# fie.net
KiCad netlist of a schematic drawn in EAGLE
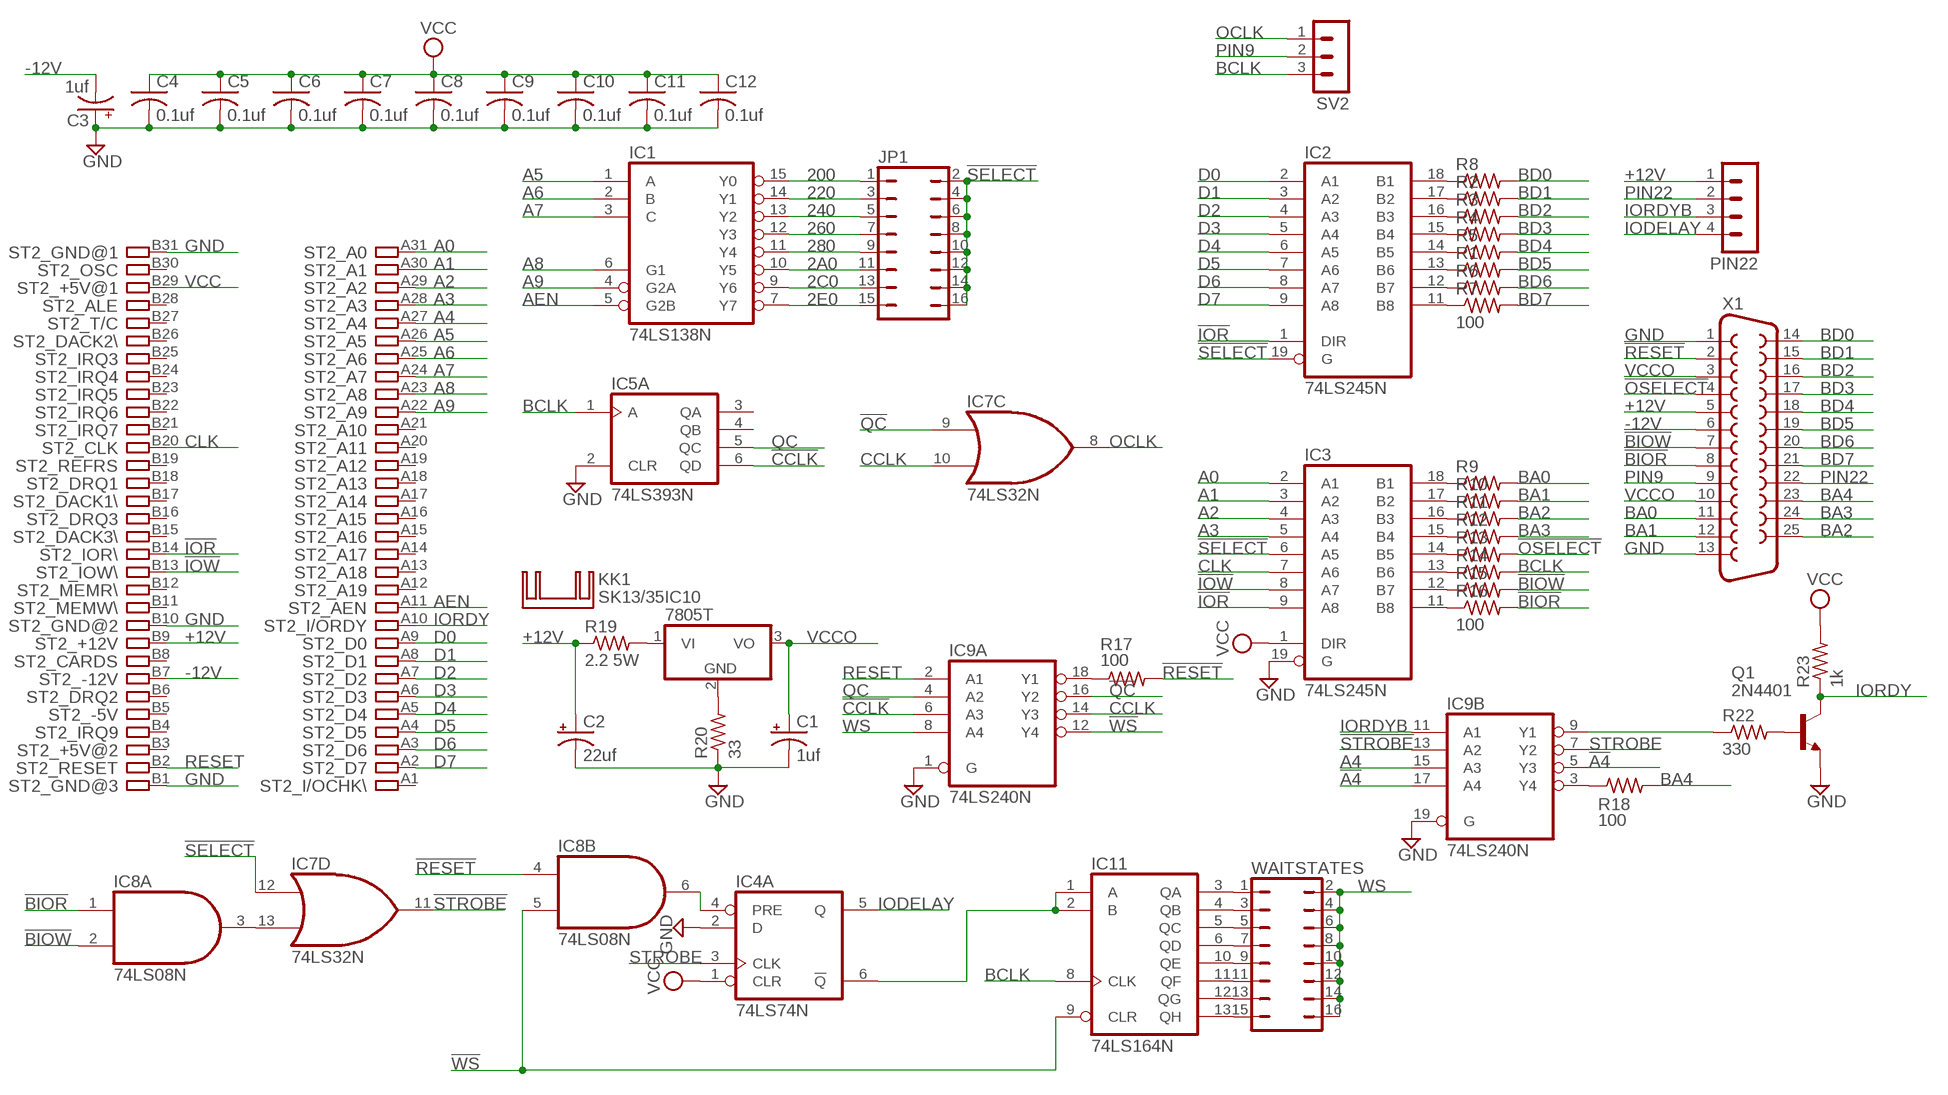
[diagram p0: schematic, sheet 1]

(export (version "E")
  (design (tool "Eeschema 10.0.6"))
  (components
    (comp (ref "C1")
      (value "1uf")
      (footprint "eagle-import:E5-10,5")
      (libsource (lib "eagle-import") (part "CPOL-USE5-10.5"))
    )
    (comp (ref "C2")
      (value "22uf")
      (footprint "eagle-import:E5-10,5")
      (libsource (lib "eagle-import") (part "CPOL-USE5-10.5"))
    )
    (comp (ref "C3")
      (value "1uf")
      (footprint "eagle-import:E5-10,5")
      (libsource (lib "eagle-import") (part "CPOL-USE5-10.5"))
    )
    (comp (ref "C4")
      (value "0.1uf")
      (footprint "eagle-import:C050-025X075")
      (libsource (lib "eagle-import") (part "C-US050-025X075"))
    )
    (comp (ref "C5")
      (value "0.1uf")
      (footprint "eagle-import:C050-025X075")
      (libsource (lib "eagle-import") (part "C-US050-025X075"))
    )
    (comp (ref "C6")
      (value "0.1uf")
      (footprint "eagle-import:C050-025X075")
      (libsource (lib "eagle-import") (part "C-US050-025X075"))
    )
    (comp (ref "C7")
      (value "0.1uf")
      (footprint "eagle-import:C050-025X075")
      (libsource (lib "eagle-import") (part "C-US050-025X075"))
    )
    (comp (ref "C8")
      (value "0.1uf")
      (footprint "eagle-import:C050-025X075")
      (libsource (lib "eagle-import") (part "C-US050-025X075"))
    )
    (comp (ref "C9")
      (value "0.1uf")
      (footprint "eagle-import:C050-025X075")
      (libsource (lib "eagle-import") (part "C-US050-025X075"))
    )
    (comp (ref "C10")
      (value "0.1uf")
      (footprint "eagle-import:C050-025X075")
      (libsource (lib "eagle-import") (part "C-US050-025X075"))
    )
    (comp (ref "C11")
      (value "0.1uf")
      (footprint "eagle-import:C050-025X075")
      (libsource (lib "eagle-import") (part "C-US050-025X075"))
    )
    (comp (ref "C12")
      (value "0.1uf")
      (footprint "eagle-import:C050-025X075")
      (libsource (lib "eagle-import") (part "C-US050-025X075"))
    )
    (comp (ref "IC1")
      (value "74LS138N")
      (footprint "eagle-import:DIL16")
      (libsource (lib "eagle-import") (part "74138NLS"))
    )
    (comp (ref "IC2")
      (value "74LS245N")
      (footprint "eagle-import:DIL20")
      (libsource (lib "eagle-import") (part "74245NLS"))
    )
    (comp (ref "IC3")
      (value "74LS245N")
      (footprint "eagle-import:DIL20")
      (libsource (lib "eagle-import") (part "74245NLS"))
    )
    (comp (ref "IC4")
      (value "74LS74N")
      (footprint "eagle-import:DIL14")
      (libsource (lib "eagle-import") (part "7474NLS"))
    )
    (comp (ref "IC5")
      (value "74LS393N")
      (footprint "eagle-import:DIL14")
      (libsource (lib "eagle-import") (part "74393NLS"))
    )
    (comp (ref "IC7")
      (value "74LS32N")
      (footprint "eagle-import:DIL14")
      (libsource (lib "eagle-import") (part "7432NLS"))
    )
    (comp (ref "IC8")
      (value "74LS08N")
      (footprint "eagle-import:DIL14")
      (libsource (lib "eagle-import") (part "7408NLS"))
    )
    (comp (ref "IC9")
      (value "74LS240N")
      (footprint "eagle-import:DIL20")
      (libsource (lib "eagle-import") (part "74240NLS"))
    )
    (comp (ref "IC10")
      (value "7805T")
      (footprint "eagle-import:TO220H")
      (libsource (lib "eagle-import") (part "78T05"))
    )
    (comp (ref "IC11")
      (value "74LS164N")
      (footprint "eagle-import:DIL14")
      (libsource (lib "eagle-import") (part "74164NLS"))
    )
    (comp (ref "JP1")
      (value "JP8Q")
      (footprint "eagle-import:JP8Q")
      (libsource (lib "eagle-import") (part "JP8Q"))
    )
    (comp (ref "KK1")
      (value "SK13/35")
      (footprint "eagle-import:SK13_35")
      (libsource (lib "eagle-import") (part "SK13/35"))
    )
    (comp (ref "PIN22")
      (value "MA04-1")
      (footprint "eagle-import:MA04-1")
      (libsource (lib "eagle-import") (part "MA04-1"))
    )
    (comp (ref "Q1")
      (value "2N4401")
      (footprint "eagle-import:TO92")
      (libsource (lib "eagle-import") (part "2N4416"))
    )
    (comp (ref "R1")
      (value "R-US_0207/10")
      (footprint "eagle-import:0207_10")
      (libsource (lib "eagle-import") (part "R-US_0207/10"))
    )
    (comp (ref "R2")
      (value "R-US_0207/10")
      (footprint "eagle-import:0207_10")
      (libsource (lib "eagle-import") (part "R-US_0207/10"))
    )
    (comp (ref "R3")
      (value "R-US_0207/10")
      (footprint "eagle-import:0207_10")
      (libsource (lib "eagle-import") (part "R-US_0207/10"))
    )
    (comp (ref "R4")
      (value "R-US_0207/10")
      (footprint "eagle-import:0207_10")
      (libsource (lib "eagle-import") (part "R-US_0207/10"))
    )
    (comp (ref "R5")
      (value "R-US_0207/10")
      (footprint "eagle-import:0207_10")
      (libsource (lib "eagle-import") (part "R-US_0207/10"))
    )
    (comp (ref "R6")
      (value "R-US_0207/10")
      (footprint "eagle-import:0207_10")
      (libsource (lib "eagle-import") (part "R-US_0207/10"))
    )
    (comp (ref "R7")
      (value "100")
      (footprint "eagle-import:0207_10")
      (libsource (lib "eagle-import") (part "R-US_0207/10"))
    )
    (comp (ref "R8")
      (value "R-US_0207/10")
      (footprint "eagle-import:0207_10")
      (libsource (lib "eagle-import") (part "R-US_0207/10"))
    )
    (comp (ref "R9")
      (value "R-US_0207/10")
      (footprint "eagle-import:0207_10")
      (libsource (lib "eagle-import") (part "R-US_0207/10"))
    )
    (comp (ref "R10")
      (value "R-US_0207/10")
      (footprint "eagle-import:0207_10")
      (libsource (lib "eagle-import") (part "R-US_0207/10"))
    )
    (comp (ref "R11")
      (value "R-US_0207/10")
      (footprint "eagle-import:0207_10")
      (libsource (lib "eagle-import") (part "R-US_0207/10"))
    )
    (comp (ref "R12")
      (value "R-US_0207/10")
      (footprint "eagle-import:0207_10")
      (libsource (lib "eagle-import") (part "R-US_0207/10"))
    )
    (comp (ref "R13")
      (value "R-US_0207/10")
      (footprint "eagle-import:0207_10")
      (libsource (lib "eagle-import") (part "R-US_0207/10"))
    )
    (comp (ref "R14")
      (value "R-US_0207/10")
      (footprint "eagle-import:0207_10")
      (libsource (lib "eagle-import") (part "R-US_0207/10"))
    )
    (comp (ref "R15")
      (value "R-US_0207/10")
      (footprint "eagle-import:0207_10")
      (libsource (lib "eagle-import") (part "R-US_0207/10"))
    )
    (comp (ref "R16")
      (value "100")
      (footprint "eagle-import:0207_10")
      (libsource (lib "eagle-import") (part "R-US_0207/10"))
    )
    (comp (ref "R17")
      (value "100")
      (footprint "eagle-import:0207_10")
      (libsource (lib "eagle-import") (part "R-US_0207/10"))
    )
    (comp (ref "R18")
      (value "100")
      (footprint "eagle-import:0207_10")
      (libsource (lib "eagle-import") (part "R-US_0207/10"))
    )
    (comp (ref "R19")
      (value "2.2 5W")
      (footprint "eagle-import:0922_22")
      (libsource (lib "eagle-import") (part "R-US_0922/22"))
    )
    (comp (ref "R20")
      (value "33")
      (footprint "eagle-import:0207_10")
      (libsource (lib "eagle-import") (part "R-US_0207/10"))
    )
    (comp (ref "R22")
      (value "330")
      (footprint "eagle-import:0207_10")
      (libsource (lib "eagle-import") (part "R-US_0207/10"))
    )
    (comp (ref "R23")
      (value "1k")
      (footprint "eagle-import:0207_10")
      (libsource (lib "eagle-import") (part "R-US_0207/10"))
    )
    (comp (ref "ST2")
      (value "IBM8BIT")
      (footprint "eagle-import:IBM8BIT")
      (libsource (lib "eagle-import") (part "IBM8BIT"))
    )
    (comp (ref "SV2")
      (value "MA03-1")
      (footprint "eagle-import:MA03-1")
      (libsource (lib "eagle-import") (part "MA03-1"))
    )
    (comp (ref "WAITSTATES")
      (value "JP8Q")
      (footprint "eagle-import:JP8Q")
      (libsource (lib "eagle-import") (part "JP8Q"))
    )
    (comp (ref "X1")
      (value "F25H")
      (footprint "eagle-import:F25H")
      (libsource (lib "eagle-import") (part "F25H"))
    )
  )
  (nets
    (net (code "1") (name "/+12V") (class "Default")
      (node (ref "C2") (pin "+") (pinfunction "+_+") (pintype "passive"))
      (node (ref "PIN22") (pin "1") (pinfunction "1_1") (pintype "passive"))
      (node (ref "R19") (pin "1") (pinfunction "1_1") (pintype "passive"))
      (node (ref "ST2") (pin "B9") (pinfunction "P_B9") (pintype "bidirectional"))
      (node (ref "X1") (pin "5") (pinfunction "5_5") (pintype "passive"))
    )
    (net (code "2") (name "/-12V") (class "Default")
      (node (ref "C3") (pin "-") (pinfunction "-_-") (pintype "passive"))
      (node (ref "ST2") (pin "B7") (pinfunction "P_B7") (pintype "bidirectional"))
      (node (ref "X1") (pin "6") (pinfunction "6_6") (pintype "passive"))
    )
    (net (code "3") (name "/2A0") (class "Default")
      (node (ref "IC1") (pin "10") (pinfunction "Y5_10") (pintype "output"))
      (node (ref "JP1") (pin "11") (pinfunction "11_11") (pintype "passive"))
    )
    (net (code "4") (name "/2C0") (class "Default")
      (node (ref "IC1") (pin "9") (pinfunction "Y6_9") (pintype "output"))
      (node (ref "JP1") (pin "13") (pinfunction "13_13") (pintype "passive"))
    )
    (net (code "5") (name "/2E0") (class "Default")
      (node (ref "IC1") (pin "7") (pinfunction "Y7_7") (pintype "output"))
      (node (ref "JP1") (pin "15") (pinfunction "15_15") (pintype "passive"))
    )
    (net (code "6") (name "/200") (class "Default")
      (node (ref "IC1") (pin "15") (pinfunction "Y0_15") (pintype "output"))
      (node (ref "JP1") (pin "1") (pinfunction "1_1") (pintype "passive"))
    )
    (net (code "7") (name "/220") (class "Default")
      (node (ref "IC1") (pin "14") (pinfunction "Y1_14") (pintype "output"))
      (node (ref "JP1") (pin "3") (pinfunction "3_3") (pintype "passive"))
    )
    (net (code "8") (name "/240") (class "Default")
      (node (ref "IC1") (pin "13") (pinfunction "Y2_13") (pintype "output"))
      (node (ref "JP1") (pin "5") (pinfunction "5_5") (pintype "passive"))
    )
    (net (code "9") (name "/260") (class "Default")
      (node (ref "IC1") (pin "12") (pinfunction "Y3_12") (pintype "output"))
      (node (ref "JP1") (pin "7") (pinfunction "7_7") (pintype "passive"))
    )
    (net (code "10") (name "/280") (class "Default")
      (node (ref "IC1") (pin "11") (pinfunction "Y4_11") (pintype "output"))
      (node (ref "JP1") (pin "9") (pinfunction "9_9") (pintype "passive"))
    )
    (net (code "11") (name "/A0") (class "Default")
      (node (ref "IC3") (pin "2") (pinfunction "A1_2") (pintype "bidirectional"))
      (node (ref "ST2") (pin "A31") (pinfunction "P_A31") (pintype "bidirectional"))
    )
    (net (code "12") (name "/A1") (class "Default")
      (node (ref "IC3") (pin "3") (pinfunction "A2_3") (pintype "bidirectional"))
      (node (ref "ST2") (pin "A30") (pinfunction "P_A30") (pintype "bidirectional"))
    )
    (net (code "13") (name "/A2") (class "Default")
      (node (ref "IC3") (pin "4") (pinfunction "A3_4") (pintype "bidirectional"))
      (node (ref "ST2") (pin "A29") (pinfunction "P_A29") (pintype "bidirectional"))
    )
    (net (code "14") (name "/A3") (class "Default")
      (node (ref "IC3") (pin "5") (pinfunction "A4_5") (pintype "bidirectional"))
      (node (ref "ST2") (pin "A28") (pinfunction "P_A28") (pintype "bidirectional"))
    )
    (net (code "15") (name "/A4") (class "Default")
      (node (ref "IC9") (pin "15") (pinfunction "A3_15") (pintype "input"))
      (node (ref "ST2") (pin "A27") (pinfunction "P_A27") (pintype "bidirectional"))
    )
    (net (code "16") (name "/A5") (class "Default")
      (node (ref "IC1") (pin "1") (pinfunction "A_1") (pintype "input"))
      (node (ref "ST2") (pin "A26") (pinfunction "P_A26") (pintype "bidirectional"))
    )
    (net (code "17") (name "/A6") (class "Default")
      (node (ref "IC1") (pin "2") (pinfunction "B_2") (pintype "input"))
      (node (ref "ST2") (pin "A25") (pinfunction "P_A25") (pintype "bidirectional"))
    )
    (net (code "18") (name "/A7") (class "Default")
      (node (ref "IC1") (pin "3") (pinfunction "C_3") (pintype "input"))
      (node (ref "ST2") (pin "A24") (pinfunction "P_A24") (pintype "bidirectional"))
    )
    (net (code "19") (name "/A8") (class "Default")
      (node (ref "IC1") (pin "6") (pinfunction "G1_6") (pintype "input"))
      (node (ref "ST2") (pin "A23") (pinfunction "P_A23") (pintype "bidirectional"))
    )
    (net (code "20") (name "/A9") (class "Default")
      (node (ref "IC1") (pin "4") (pinfunction "G2A_4") (pintype "input"))
      (node (ref "ST2") (pin "A22") (pinfunction "P_A22") (pintype "bidirectional"))
    )
    (net (code "21") (name "/AEN") (class "Default")
      (node (ref "IC1") (pin "5") (pinfunction "G2B_5") (pintype "input"))
      (node (ref "ST2") (pin "A11") (pinfunction "P_A11") (pintype "bidirectional"))
    )
    (net (code "22") (name "/BA0") (class "Default")
      (node (ref "R9") (pin "2") (pinfunction "2_2") (pintype "passive"))
      (node (ref "X1") (pin "11") (pinfunction "11_11") (pintype "passive"))
    )
    (net (code "23") (name "/BA1") (class "Default")
      (node (ref "R10") (pin "2") (pinfunction "2_2") (pintype "passive"))
      (node (ref "X1") (pin "12") (pinfunction "12_12") (pintype "passive"))
    )
    (net (code "24") (name "/BA2") (class "Default")
      (node (ref "R11") (pin "2") (pinfunction "2_2") (pintype "passive"))
      (node (ref "X1") (pin "25") (pinfunction "25_25") (pintype "passive"))
    )
    (net (code "25") (name "/BA3") (class "Default")
      (node (ref "R12") (pin "2") (pinfunction "2_2") (pintype "passive"))
      (node (ref "X1") (pin "24") (pinfunction "24_24") (pintype "passive"))
    )
    (net (code "26") (name "/BA4") (class "Default")
      (node (ref "R18") (pin "2") (pinfunction "2_2") (pintype "passive"))
      (node (ref "X1") (pin "23") (pinfunction "23_23") (pintype "passive"))
    )
    (net (code "27") (name "/BCLK") (class "Default")
      (node (ref "IC11") (pin "8") (pinfunction "CLK_8") (pintype "input"))
      (node (ref "IC5") (pin "1") (pinfunction "A_1") (pintype "input"))
      (node (ref "R14") (pin "2") (pinfunction "2_2") (pintype "passive"))
      (node (ref "SV2") (pin "3") (pinfunction "3_3") (pintype "passive"))
    )
    (net (code "28") (name "/BD0") (class "Default")
      (node (ref "R8") (pin "2") (pinfunction "2_2") (pintype "passive"))
      (node (ref "X1") (pin "14") (pinfunction "14_14") (pintype "passive"))
    )
    (net (code "29") (name "/BD1") (class "Default")
      (node (ref "R2") (pin "2") (pinfunction "2_2") (pintype "passive"))
      (node (ref "X1") (pin "15") (pinfunction "15_15") (pintype "passive"))
    )
    (net (code "30") (name "/BD2") (class "Default")
      (node (ref "R3") (pin "2") (pinfunction "2_2") (pintype "passive"))
      (node (ref "X1") (pin "16") (pinfunction "16_16") (pintype "passive"))
    )
    (net (code "31") (name "/BD3") (class "Default")
      (node (ref "R4") (pin "2") (pinfunction "2_2") (pintype "passive"))
      (node (ref "X1") (pin "17") (pinfunction "17_17") (pintype "passive"))
    )
    (net (code "32") (name "/BD4") (class "Default")
      (node (ref "R5") (pin "2") (pinfunction "2_2") (pintype "passive"))
      (node (ref "X1") (pin "18") (pinfunction "18_18") (pintype "passive"))
    )
    (net (code "33") (name "/BD5") (class "Default")
      (node (ref "R1") (pin "2") (pinfunction "2_2") (pintype "passive"))
      (node (ref "X1") (pin "19") (pinfunction "19_19") (pintype "passive"))
    )
    (net (code "34") (name "/BD6") (class "Default")
      (node (ref "R6") (pin "2") (pinfunction "2_2") (pintype "passive"))
      (node (ref "X1") (pin "20") (pinfunction "20_20") (pintype "passive"))
    )
    (net (code "35") (name "/BD7") (class "Default")
      (node (ref "R7") (pin "2") (pinfunction "2_2") (pintype "passive"))
      (node (ref "X1") (pin "21") (pinfunction "21_21") (pintype "passive"))
    )
    (net (code "36") (name "/CCLK") (class "Default")
      (node (ref "IC7") (pin "10") (pinfunction "I1_10") (pintype "input"))
      (node (ref "IC9") (pin "14") (pinfunction "Y3_14") (pintype "tri_state"))
    )
    (net (code "37") (name "/CLK") (class "Default")
      (node (ref "IC3") (pin "7") (pinfunction "A6_7") (pintype "bidirectional"))
      (node (ref "ST2") (pin "B20") (pinfunction "P_B20") (pintype "bidirectional"))
    )
    (net (code "38") (name "/D0") (class "Default")
      (node (ref "IC2") (pin "2") (pinfunction "A1_2") (pintype "bidirectional"))
      (node (ref "ST2") (pin "A9") (pinfunction "P_A9") (pintype "bidirectional"))
    )
    (net (code "39") (name "/D1") (class "Default")
      (node (ref "IC2") (pin "3") (pinfunction "A2_3") (pintype "bidirectional"))
      (node (ref "ST2") (pin "A8") (pinfunction "P_A8") (pintype "bidirectional"))
    )
    (net (code "40") (name "/D2") (class "Default")
      (node (ref "IC2") (pin "4") (pinfunction "A3_4") (pintype "bidirectional"))
      (node (ref "ST2") (pin "A7") (pinfunction "P_A7") (pintype "bidirectional"))
    )
    (net (code "41") (name "/D3") (class "Default")
      (node (ref "IC2") (pin "5") (pinfunction "A4_5") (pintype "bidirectional"))
      (node (ref "ST2") (pin "A6") (pinfunction "P_A6") (pintype "bidirectional"))
    )
    (net (code "42") (name "/D4") (class "Default")
      (node (ref "IC2") (pin "6") (pinfunction "A5_6") (pintype "bidirectional"))
      (node (ref "ST2") (pin "A5") (pinfunction "P_A5") (pintype "bidirectional"))
    )
    (net (code "43") (name "/D5") (class "Default")
      (node (ref "IC2") (pin "7") (pinfunction "A6_7") (pintype "bidirectional"))
      (node (ref "ST2") (pin "A4") (pinfunction "P_A4") (pintype "bidirectional"))
    )
    (net (code "44") (name "/D6") (class "Default")
      (node (ref "IC2") (pin "8") (pinfunction "A7_8") (pintype "bidirectional"))
      (node (ref "ST2") (pin "A3") (pinfunction "P_A3") (pintype "bidirectional"))
    )
    (net (code "45") (name "/D7") (class "Default")
      (node (ref "IC2") (pin "9") (pinfunction "A8_9") (pintype "bidirectional"))
      (node (ref "ST2") (pin "A2") (pinfunction "P_A2") (pintype "bidirectional"))
    )
    (net (code "46") (name "/IODELAY") (class "Default")
      (node (ref "IC4") (pin "5") (pinfunction "Q_5") (pintype "output"))
      (node (ref "PIN22") (pin "4") (pinfunction "4_4") (pintype "passive"))
    )
    (net (code "47") (name "/IORDY") (class "Default")
      (node (ref "Q1") (pin "1") (pinfunction "C_1") (pintype "passive"))
      (node (ref "R23") (pin "1") (pinfunction "1_1") (pintype "passive"))
      (node (ref "ST2") (pin "A10") (pinfunction "P_A10") (pintype "bidirectional"))
    )
    (net (code "48") (name "/IORDYB") (class "Default")
      (node (ref "IC9") (pin "11") (pinfunction "A1_11") (pintype "input"))
      (node (ref "PIN22") (pin "3") (pinfunction "3_3") (pintype "passive"))
    )
    (net (code "49") (name "/OCLK") (class "Default")
      (node (ref "IC7") (pin "8") (pinfunction "O_8") (pintype "output"))
      (node (ref "SV2") (pin "1") (pinfunction "1_1") (pintype "passive"))
    )
    (net (code "50") (name "/PIN9") (class "Default")
      (node (ref "SV2") (pin "2") (pinfunction "2_2") (pintype "passive"))
      (node (ref "X1") (pin "9") (pinfunction "9_9") (pintype "passive"))
    )
    (net (code "51") (name "/PIN22") (class "Default")
      (node (ref "PIN22") (pin "2") (pinfunction "2_2") (pintype "passive"))
      (node (ref "X1") (pin "22") (pinfunction "22_22") (pintype "passive"))
    )
    (net (code "52") (name "/QC") (class "Default")
      (node (ref "IC5") (pin "5") (pinfunction "QC_5") (pintype "output"))
      (node (ref "IC9") (pin "4") (pinfunction "A2_4") (pintype "input"))
    )
    (net (code "53") (name "/RESET") (class "Default")
      (node (ref "IC9") (pin "2") (pinfunction "A1_2") (pintype "input"))
      (node (ref "ST2") (pin "B2") (pinfunction "P_B2") (pintype "bidirectional"))
    )
    (net (code "54") (name "/STROBE") (class "Default")
      (node (ref "IC4") (pin "3") (pinfunction "CLK_3") (pintype "input"))
      (node (ref "IC9") (pin "7") (pinfunction "Y2_7") (pintype "tri_state"))
    )
    (net (code "55") (name "/VCCO") (class "Default")
      (node (ref "C1") (pin "+") (pinfunction "+_+") (pintype "passive"))
      (node (ref "IC10") (pin "3") (pinfunction "VO_3") (pintype "passive"))
      (node (ref "X1") (pin "10") (pinfunction "10_10") (pintype "passive"))
      (node (ref "X1") (pin "3") (pinfunction "3_3") (pintype "passive"))
    )
    (net (code "56") (name "/WS") (class "Default")
      (node (ref "IC9") (pin "8") (pinfunction "A4_8") (pintype "input"))
      (node (ref "WAITSTATES") (pin "10") (pinfunction "10_10") (pintype "passive"))
      (node (ref "WAITSTATES") (pin "12") (pinfunction "12_12") (pintype "passive"))
      (node (ref "WAITSTATES") (pin "14") (pinfunction "14_14") (pintype "passive"))
      (node (ref "WAITSTATES") (pin "16") (pinfunction "16_16") (pintype "passive"))
      (node (ref "WAITSTATES") (pin "2") (pinfunction "2_2") (pintype "passive"))
      (node (ref "WAITSTATES") (pin "4") (pinfunction "4_4") (pintype "passive"))
      (node (ref "WAITSTATES") (pin "6") (pinfunction "6_6") (pintype "passive"))
      (node (ref "WAITSTATES") (pin "8") (pinfunction "8_8") (pintype "passive"))
    )
    (net (code "57") (name "/~{A4}") (class "Default")
      (node (ref "IC9") (pin "17") (pinfunction "A4_17") (pintype "input"))
      (node (ref "IC9") (pin "5") (pinfunction "Y3_5") (pintype "tri_state"))
    )
    (net (code "58") (name "/~{BIOR}") (class "Default")
      (node (ref "IC8") (pin "1") (pinfunction "I0_1") (pintype "input"))
      (node (ref "R16") (pin "2") (pinfunction "2_2") (pintype "passive"))
      (node (ref "X1") (pin "8") (pinfunction "8_8") (pintype "passive"))
    )
    (net (code "59") (name "/~{BIOW}") (class "Default")
      (node (ref "IC8") (pin "2") (pinfunction "I1_2") (pintype "input"))
      (node (ref "R15") (pin "2") (pinfunction "2_2") (pintype "passive"))
      (node (ref "X1") (pin "7") (pinfunction "7_7") (pintype "passive"))
    )
    (net (code "60") (name "/~{CCLK}") (class "Default")
      (node (ref "IC5") (pin "6") (pinfunction "QD_6") (pintype "output"))
      (node (ref "IC9") (pin "6") (pinfunction "A3_6") (pintype "input"))
    )
    (net (code "61") (name "/~{IOR}") (class "Default")
      (node (ref "IC2") (pin "1") (pinfunction "DIR_1") (pintype "input"))
      (node (ref "IC3") (pin "9") (pinfunction "A8_9") (pintype "bidirectional"))
      (node (ref "ST2") (pin "B14") (pinfunction "P_B14") (pintype "bidirectional"))
    )
    (net (code "62") (name "/~{IOW}") (class "Default")
      (node (ref "IC3") (pin "8") (pinfunction "A7_8") (pintype "bidirectional"))
      (node (ref "ST2") (pin "B13") (pinfunction "P_B13") (pintype "bidirectional"))
    )
    (net (code "63") (name "/~{OSELECT}") (class "Default")
      (node (ref "R13") (pin "2") (pinfunction "2_2") (pintype "passive"))
      (node (ref "X1") (pin "4") (pinfunction "4_4") (pintype "passive"))
    )
    (net (code "64") (name "/~{QC}") (class "Default")
      (node (ref "IC7") (pin "9") (pinfunction "I0_9") (pintype "input"))
      (node (ref "IC9") (pin "16") (pinfunction "Y2_16") (pintype "tri_state"))
    )
    (net (code "65") (name "/~{RESET}") (class "Default")
      (node (ref "IC8") (pin "4") (pinfunction "I0_4") (pintype "input"))
      (node (ref "R17") (pin "2") (pinfunction "2_2") (pintype "passive"))
      (node (ref "X1") (pin "2") (pinfunction "2_2") (pintype "passive"))
    )
    (net (code "66") (name "/~{SELECT}") (class "Default")
      (node (ref "IC2") (pin "19") (pinfunction "G_19") (pintype "input"))
      (node (ref "IC3") (pin "6") (pinfunction "A5_6") (pintype "bidirectional"))
      (node (ref "IC7") (pin "12") (pinfunction "I0_12") (pintype "input"))
      (node (ref "JP1") (pin "10") (pinfunction "10_10") (pintype "passive"))
      (node (ref "JP1") (pin "12") (pinfunction "12_12") (pintype "passive"))
      (node (ref "JP1") (pin "14") (pinfunction "14_14") (pintype "passive"))
      (node (ref "JP1") (pin "16") (pinfunction "16_16") (pintype "passive"))
      (node (ref "JP1") (pin "2") (pinfunction "2_2") (pintype "passive"))
      (node (ref "JP1") (pin "4") (pinfunction "4_4") (pintype "passive"))
      (node (ref "JP1") (pin "6") (pinfunction "6_6") (pintype "passive"))
      (node (ref "JP1") (pin "8") (pinfunction "8_8") (pintype "passive"))
    )
    (net (code "67") (name "/~{STROBE}") (class "Default")
      (node (ref "IC7") (pin "11") (pinfunction "O_11") (pintype "output"))
      (node (ref "IC9") (pin "13") (pinfunction "A2_13") (pintype "input"))
    )
    (net (code "68") (name "/~{WS}") (class "Default")
      (node (ref "IC11") (pin "9") (pinfunction "CLR_9") (pintype "input"))
      (node (ref "IC8") (pin "5") (pinfunction "I1_5") (pintype "input"))
      (node (ref "IC9") (pin "12") (pinfunction "Y4_12") (pintype "tri_state"))
    )
    (net (code "69") (name "GND") (class "Default")
      (node (ref "C1") (pin "-") (pinfunction "-_-") (pintype "passive"))
      (node (ref "C10") (pin "2") (pinfunction "2_2") (pintype "passive"))
      (node (ref "C11") (pin "2") (pinfunction "2_2") (pintype "passive"))
      (node (ref "C12") (pin "2") (pinfunction "2_2") (pintype "passive"))
      (node (ref "C2") (pin "-") (pinfunction "-_-") (pintype "passive"))
      (node (ref "C3") (pin "+") (pinfunction "+_+") (pintype "passive"))
      (node (ref "C4") (pin "2") (pinfunction "2_2") (pintype "passive"))
      (node (ref "C5") (pin "2") (pinfunction "2_2") (pintype "passive"))
      (node (ref "C6") (pin "2") (pinfunction "2_2") (pintype "passive"))
      (node (ref "C7") (pin "2") (pinfunction "2_2") (pintype "passive"))
      (node (ref "C8") (pin "2") (pinfunction "2_2") (pintype "passive"))
      (node (ref "C9") (pin "2") (pinfunction "2_2") (pintype "passive"))
      (node (ref "IC3") (pin "19") (pinfunction "G_19") (pintype "input"))
      (node (ref "IC4") (pin "2") (pinfunction "D_2") (pintype "input"))
      (node (ref "IC5") (pin "2") (pinfunction "CLR_2") (pintype "input"))
      (node (ref "IC9") (pin "1") (pinfunction "G_1") (pintype "input"))
      (node (ref "IC9") (pin "19") (pinfunction "G_19") (pintype "input"))
      (node (ref "Q1") (pin "3") (pinfunction "E_3") (pintype "passive"))
      (node (ref "R20") (pin "1") (pinfunction "1_1") (pintype "passive"))
      (node (ref "ST2") (pin "B1") (pinfunction "P_B1") (pintype "bidirectional"))
      (node (ref "ST2") (pin "B10") (pinfunction "P_B10") (pintype "bidirectional"))
      (node (ref "ST2") (pin "B31") (pinfunction "P_B31") (pintype "bidirectional"))
      (node (ref "X1") (pin "1") (pinfunction "1_1") (pintype "passive"))
      (node (ref "X1") (pin "13") (pinfunction "13_13") (pintype "passive"))
    )
    (net (code "70") (name "Net-(IC2A-B1)") (class "Default")
      (node (ref "IC2") (pin "18") (pinfunction "B1_18") (pintype "bidirectional"))
      (node (ref "R8") (pin "1") (pinfunction "1_1") (pintype "passive"))
    )
    (net (code "71") (name "Net-(IC2A-B2)") (class "Default")
      (node (ref "IC2") (pin "17") (pinfunction "B2_17") (pintype "bidirectional"))
      (node (ref "R2") (pin "1") (pinfunction "1_1") (pintype "passive"))
    )
    (net (code "72") (name "Net-(IC2A-B3)") (class "Default")
      (node (ref "IC2") (pin "16") (pinfunction "B3_16") (pintype "bidirectional"))
      (node (ref "R3") (pin "1") (pinfunction "1_1") (pintype "passive"))
    )
    (net (code "73") (name "Net-(IC2A-B4)") (class "Default")
      (node (ref "IC2") (pin "15") (pinfunction "B4_15") (pintype "bidirectional"))
      (node (ref "R4") (pin "1") (pinfunction "1_1") (pintype "passive"))
    )
    (net (code "74") (name "Net-(IC2A-B5)") (class "Default")
      (node (ref "IC2") (pin "14") (pinfunction "B5_14") (pintype "bidirectional"))
      (node (ref "R5") (pin "1") (pinfunction "1_1") (pintype "passive"))
    )
    (net (code "75") (name "Net-(IC2A-B6)") (class "Default")
      (node (ref "IC2") (pin "13") (pinfunction "B6_13") (pintype "bidirectional"))
      (node (ref "R1") (pin "1") (pinfunction "1_1") (pintype "passive"))
    )
    (net (code "76") (name "Net-(IC2A-B7)") (class "Default")
      (node (ref "IC2") (pin "12") (pinfunction "B7_12") (pintype "bidirectional"))
      (node (ref "R6") (pin "1") (pinfunction "1_1") (pintype "passive"))
    )
    (net (code "77") (name "Net-(IC2A-B8)") (class "Default")
      (node (ref "IC2") (pin "11") (pinfunction "B8_11") (pintype "bidirectional"))
      (node (ref "R7") (pin "1") (pinfunction "1_1") (pintype "passive"))
    )
    (net (code "78") (name "Net-(IC3A-B1)") (class "Default")
      (node (ref "IC3") (pin "18") (pinfunction "B1_18") (pintype "bidirectional"))
      (node (ref "R9") (pin "1") (pinfunction "1_1") (pintype "passive"))
    )
    (net (code "79") (name "Net-(IC3A-B2)") (class "Default")
      (node (ref "IC3") (pin "17") (pinfunction "B2_17") (pintype "bidirectional"))
      (node (ref "R10") (pin "1") (pinfunction "1_1") (pintype "passive"))
    )
    (net (code "80") (name "Net-(IC3A-B3)") (class "Default")
      (node (ref "IC3") (pin "16") (pinfunction "B3_16") (pintype "bidirectional"))
      (node (ref "R11") (pin "1") (pinfunction "1_1") (pintype "passive"))
    )
    (net (code "81") (name "Net-(IC3A-B4)") (class "Default")
      (node (ref "IC3") (pin "15") (pinfunction "B4_15") (pintype "bidirectional"))
      (node (ref "R12") (pin "1") (pinfunction "1_1") (pintype "passive"))
    )
    (net (code "82") (name "Net-(IC3A-B5)") (class "Default")
      (node (ref "IC3") (pin "14") (pinfunction "B5_14") (pintype "bidirectional"))
      (node (ref "R13") (pin "1") (pinfunction "1_1") (pintype "passive"))
    )
    (net (code "83") (name "Net-(IC3A-B6)") (class "Default")
      (node (ref "IC3") (pin "13") (pinfunction "B6_13") (pintype "bidirectional"))
      (node (ref "R14") (pin "1") (pinfunction "1_1") (pintype "passive"))
    )
    (net (code "84") (name "Net-(IC3A-B7)") (class "Default")
      (node (ref "IC3") (pin "12") (pinfunction "B7_12") (pintype "bidirectional"))
      (node (ref "R15") (pin "1") (pinfunction "1_1") (pintype "passive"))
    )
    (net (code "85") (name "Net-(IC3A-B8)") (class "Default")
      (node (ref "IC3") (pin "11") (pinfunction "B8_11") (pintype "bidirectional"))
      (node (ref "R16") (pin "1") (pinfunction "1_1") (pintype "passive"))
    )
    (net (code "86") (name "Net-(IC4A-PRE)") (class "Default")
      (node (ref "IC4") (pin "4") (pinfunction "PRE_4") (pintype "input"))
      (node (ref "IC8") (pin "6") (pinfunction "O_6") (pintype "output"))
    )
    (net (code "87") (name "Net-(IC7D-I1)") (class "Default")
      (node (ref "IC7") (pin "13") (pinfunction "I1_13") (pintype "input"))
      (node (ref "IC8") (pin "3") (pinfunction "O_3") (pintype "output"))
    )
    (net (code "88") (name "Net-(IC9A-Y1)") (class "Default")
      (node (ref "IC9") (pin "18") (pinfunction "Y1_18") (pintype "tri_state"))
      (node (ref "R17") (pin "1") (pinfunction "1_1") (pintype "passive"))
    )
    (net (code "89") (name "Net-(IC9B-Y1)") (class "Default")
      (node (ref "IC9") (pin "9") (pinfunction "Y1_9") (pintype "tri_state"))
      (node (ref "R22") (pin "1") (pinfunction "1_1") (pintype "passive"))
    )
    (net (code "90") (name "Net-(IC9B-Y4)") (class "Default")
      (node (ref "IC9") (pin "3") (pinfunction "Y4_3") (pintype "tri_state"))
      (node (ref "R18") (pin "1") (pinfunction "1_1") (pintype "passive"))
    )
    (net (code "91") (name "Net-(IC10-GND)") (class "Default")
      (node (ref "IC10") (pin "2") (pinfunction "GND_2") (pintype "passive"))
      (node (ref "R20") (pin "2") (pinfunction "2_2") (pintype "passive"))
    )
    (net (code "92") (name "Net-(IC10-VI)") (class "Default")
      (node (ref "IC10") (pin "1") (pinfunction "VI_1") (pintype "input"))
      (node (ref "R19") (pin "2") (pinfunction "2_2") (pintype "passive"))
    )
    (net (code "93") (name "Net-(IC11A-A)") (class "Default")
      (node (ref "IC11") (pin "1") (pinfunction "A_1") (pintype "input"))
      (node (ref "IC11") (pin "2") (pinfunction "B_2") (pintype "input"))
      (node (ref "IC4") (pin "6") (pinfunction "~{Q}_6") (pintype "output"))
    )
    (net (code "94") (name "Net-(IC11A-QA)") (class "Default")
      (node (ref "IC11") (pin "3") (pinfunction "QA_3") (pintype "output"))
      (node (ref "WAITSTATES") (pin "1") (pinfunction "1_1") (pintype "passive"))
    )
    (net (code "95") (name "Net-(IC11A-QB)") (class "Default")
      (node (ref "IC11") (pin "4") (pinfunction "QB_4") (pintype "output"))
      (node (ref "WAITSTATES") (pin "3") (pinfunction "3_3") (pintype "passive"))
    )
    (net (code "96") (name "Net-(IC11A-QC)") (class "Default")
      (node (ref "IC11") (pin "5") (pinfunction "QC_5") (pintype "output"))
      (node (ref "WAITSTATES") (pin "5") (pinfunction "5_5") (pintype "passive"))
    )
    (net (code "97") (name "Net-(IC11A-QD)") (class "Default")
      (node (ref "IC11") (pin "6") (pinfunction "QD_6") (pintype "output"))
      (node (ref "WAITSTATES") (pin "7") (pinfunction "7_7") (pintype "passive"))
    )
    (net (code "98") (name "Net-(IC11A-QE)") (class "Default")
      (node (ref "IC11") (pin "10") (pinfunction "QE_10") (pintype "output"))
      (node (ref "WAITSTATES") (pin "9") (pinfunction "9_9") (pintype "passive"))
    )
    (net (code "99") (name "Net-(IC11A-QF)") (class "Default")
      (node (ref "IC11") (pin "11") (pinfunction "QF_11") (pintype "output"))
      (node (ref "WAITSTATES") (pin "11") (pinfunction "11_11") (pintype "passive"))
    )
    (net (code "100") (name "Net-(IC11A-QG)") (class "Default")
      (node (ref "IC11") (pin "12") (pinfunction "QG_12") (pintype "output"))
      (node (ref "WAITSTATES") (pin "13") (pinfunction "13_13") (pintype "passive"))
    )
    (net (code "101") (name "Net-(IC11A-QH)") (class "Default")
      (node (ref "IC11") (pin "13") (pinfunction "QH_13") (pintype "output"))
      (node (ref "WAITSTATES") (pin "15") (pinfunction "15_15") (pintype "passive"))
    )
    (net (code "102") (name "Net-(Q1-B)") (class "Default")
      (node (ref "Q1") (pin "2") (pinfunction "B_2") (pintype "passive"))
      (node (ref "R22") (pin "2") (pinfunction "2_2") (pintype "passive"))
    )
    (net (code "103") (name "VCC") (class "Default")
      (node (ref "C10") (pin "1") (pinfunction "1_1") (pintype "passive"))
      (node (ref "C11") (pin "1") (pinfunction "1_1") (pintype "passive"))
      (node (ref "C12") (pin "1") (pinfunction "1_1") (pintype "passive"))
      (node (ref "C4") (pin "1") (pinfunction "1_1") (pintype "passive"))
      (node (ref "C5") (pin "1") (pinfunction "1_1") (pintype "passive"))
      (node (ref "C6") (pin "1") (pinfunction "1_1") (pintype "passive"))
      (node (ref "C7") (pin "1") (pinfunction "1_1") (pintype "passive"))
      (node (ref "C8") (pin "1") (pinfunction "1_1") (pintype "passive"))
      (node (ref "C9") (pin "1") (pinfunction "1_1") (pintype "passive"))
      (node (ref "IC3") (pin "1") (pinfunction "DIR_1") (pintype "input"))
      (node (ref "IC4") (pin "1") (pinfunction "CLR_1") (pintype "input"))
      (node (ref "R23") (pin "2") (pinfunction "2_2") (pintype "passive"))
      (node (ref "ST2") (pin "B29") (pinfunction "P_B29") (pintype "bidirectional"))
    )
    (net (code "104") (name "unconnected-(IC5A-QA-Pad3)") (class "Default")
      (node (ref "IC5") (pin "3") (pinfunction "QA_3") (pintype "output"))
    )
    (net (code "105") (name "unconnected-(IC5A-QB-Pad4)") (class "Default")
      (node (ref "IC5") (pin "4") (pinfunction "QB_4") (pintype "output"))
    )
    (net (code "106") (name "unconnected-(ST2AA-P-PadB28)") (class "Default")
      (node (ref "ST2") (pin "B28") (pinfunction "P_B28") (pintype "bidirectional"))
    )
    (net (code "107") (name "unconnected-(ST2AB-P-PadB8)") (class "Default")
      (node (ref "ST2") (pin "B8") (pinfunction "P_B8") (pintype "bidirectional"))
    )
    (net (code "108") (name "unconnected-(ST2AL-P-PadB17)") (class "Default")
      (node (ref "ST2") (pin "B17") (pinfunction "P_B17") (pintype "bidirectional"))
    )
    (net (code "109") (name "unconnected-(ST2AM-P-PadB26)") (class "Default")
      (node (ref "ST2") (pin "B26") (pinfunction "P_B26") (pintype "bidirectional"))
    )
    (net (code "110") (name "unconnected-(ST2AN-P-PadB15)") (class "Default")
      (node (ref "ST2") (pin "B15") (pinfunction "P_B15") (pintype "bidirectional"))
    )
    (net (code "111") (name "unconnected-(ST2AO-P-PadB18)") (class "Default")
      (node (ref "ST2") (pin "B18") (pinfunction "P_B18") (pintype "bidirectional"))
    )
    (net (code "112") (name "unconnected-(ST2AP-P-PadB6)") (class "Default")
      (node (ref "ST2") (pin "B6") (pinfunction "P_B6") (pintype "bidirectional"))
    )
    (net (code "113") (name "unconnected-(ST2AQ-P-PadB16)") (class "Default")
      (node (ref "ST2") (pin "B16") (pinfunction "P_B16") (pintype "bidirectional"))
    )
    (net (code "114") (name "unconnected-(ST2AU-P-PadA1)") (class "Default")
      (node (ref "ST2") (pin "A1") (pinfunction "P_A1") (pintype "bidirectional"))
    )
    (net (code "115") (name "unconnected-(ST2AY-P-PadB25)") (class "Default")
      (node (ref "ST2") (pin "B25") (pinfunction "P_B25") (pintype "bidirectional"))
    )
    (net (code "116") (name "unconnected-(ST2AZ-P-PadB24)") (class "Default")
      (node (ref "ST2") (pin "B24") (pinfunction "P_B24") (pintype "bidirectional"))
    )
    (net (code "117") (name "unconnected-(ST2BA-P-PadB23)") (class "Default")
      (node (ref "ST2") (pin "B23") (pinfunction "P_B23") (pintype "bidirectional"))
    )
    (net (code "118") (name "unconnected-(ST2BB-P-PadB22)") (class "Default")
      (node (ref "ST2") (pin "B22") (pinfunction "P_B22") (pintype "bidirectional"))
    )
    (net (code "119") (name "unconnected-(ST2BC-P-PadB21)") (class "Default")
      (node (ref "ST2") (pin "B21") (pinfunction "P_B21") (pintype "bidirectional"))
    )
    (net (code "120") (name "unconnected-(ST2BD-P-PadB4)") (class "Default")
      (node (ref "ST2") (pin "B4") (pinfunction "P_B4") (pintype "bidirectional"))
    )
    (net (code "121") (name "unconnected-(ST2BE-P-PadB12)") (class "Default")
      (node (ref "ST2") (pin "B12") (pinfunction "P_B12") (pintype "bidirectional"))
    )
    (net (code "122") (name "unconnected-(ST2BF-P-PadB11)") (class "Default")
      (node (ref "ST2") (pin "B11") (pinfunction "P_B11") (pintype "bidirectional"))
    )
    (net (code "123") (name "unconnected-(ST2BG-P-PadB30)") (class "Default")
      (node (ref "ST2") (pin "B30") (pinfunction "P_B30") (pintype "bidirectional"))
    )
    (net (code "124") (name "unconnected-(ST2BH-P-PadB19)") (class "Default")
      (node (ref "ST2") (pin "B19") (pinfunction "P_B19") (pintype "bidirectional"))
    )
    (net (code "125") (name "unconnected-(ST2BJ-P-PadB27)") (class "Default")
      (node (ref "ST2") (pin "B27") (pinfunction "P_B27") (pintype "bidirectional"))
    )
    (net (code "126") (name "unconnected-(ST2C-P-PadB3)") (class "Default")
      (node (ref "ST2") (pin "B3") (pinfunction "P_B3") (pintype "bidirectional"))
    )
    (net (code "127") (name "unconnected-(ST2E-P-PadB5)") (class "Default")
      (node (ref "ST2") (pin "B5") (pinfunction "P_B5") (pintype "bidirectional"))
    )
    (net (code "128") (name "unconnected-(ST2H-P-PadA21)") (class "Default")
      (node (ref "ST2") (pin "A21") (pinfunction "P_A21") (pintype "bidirectional"))
    )
    (net (code "129") (name "unconnected-(ST2I-P-PadA20)") (class "Default")
      (node (ref "ST2") (pin "A20") (pinfunction "P_A20") (pintype "bidirectional"))
    )
    (net (code "130") (name "unconnected-(ST2J-P-PadA19)") (class "Default")
      (node (ref "ST2") (pin "A19") (pinfunction "P_A19") (pintype "bidirectional"))
    )
    (net (code "131") (name "unconnected-(ST2K-P-PadA18)") (class "Default")
      (node (ref "ST2") (pin "A18") (pinfunction "P_A18") (pintype "bidirectional"))
    )
    (net (code "132") (name "unconnected-(ST2L-P-PadA17)") (class "Default")
      (node (ref "ST2") (pin "A17") (pinfunction "P_A17") (pintype "bidirectional"))
    )
    (net (code "133") (name "unconnected-(ST2M-P-PadA16)") (class "Default")
      (node (ref "ST2") (pin "A16") (pinfunction "P_A16") (pintype "bidirectional"))
    )
    (net (code "134") (name "unconnected-(ST2N-P-PadA15)") (class "Default")
      (node (ref "ST2") (pin "A15") (pinfunction "P_A15") (pintype "bidirectional"))
    )
    (net (code "135") (name "unconnected-(ST2O-P-PadA14)") (class "Default")
      (node (ref "ST2") (pin "A14") (pinfunction "P_A14") (pintype "bidirectional"))
    )
    (net (code "136") (name "unconnected-(ST2P-P-PadA13)") (class "Default")
      (node (ref "ST2") (pin "A13") (pinfunction "P_A13") (pintype "bidirectional"))
    )
    (net (code "137") (name "unconnected-(ST2Q-P-PadA12)") (class "Default")
      (node (ref "ST2") (pin "A12") (pinfunction "P_A12") (pintype "bidirectional"))
    )
  )
)
